# TDT_CableTester.net
KiCad netlist of a schematic drawn in EAGLE
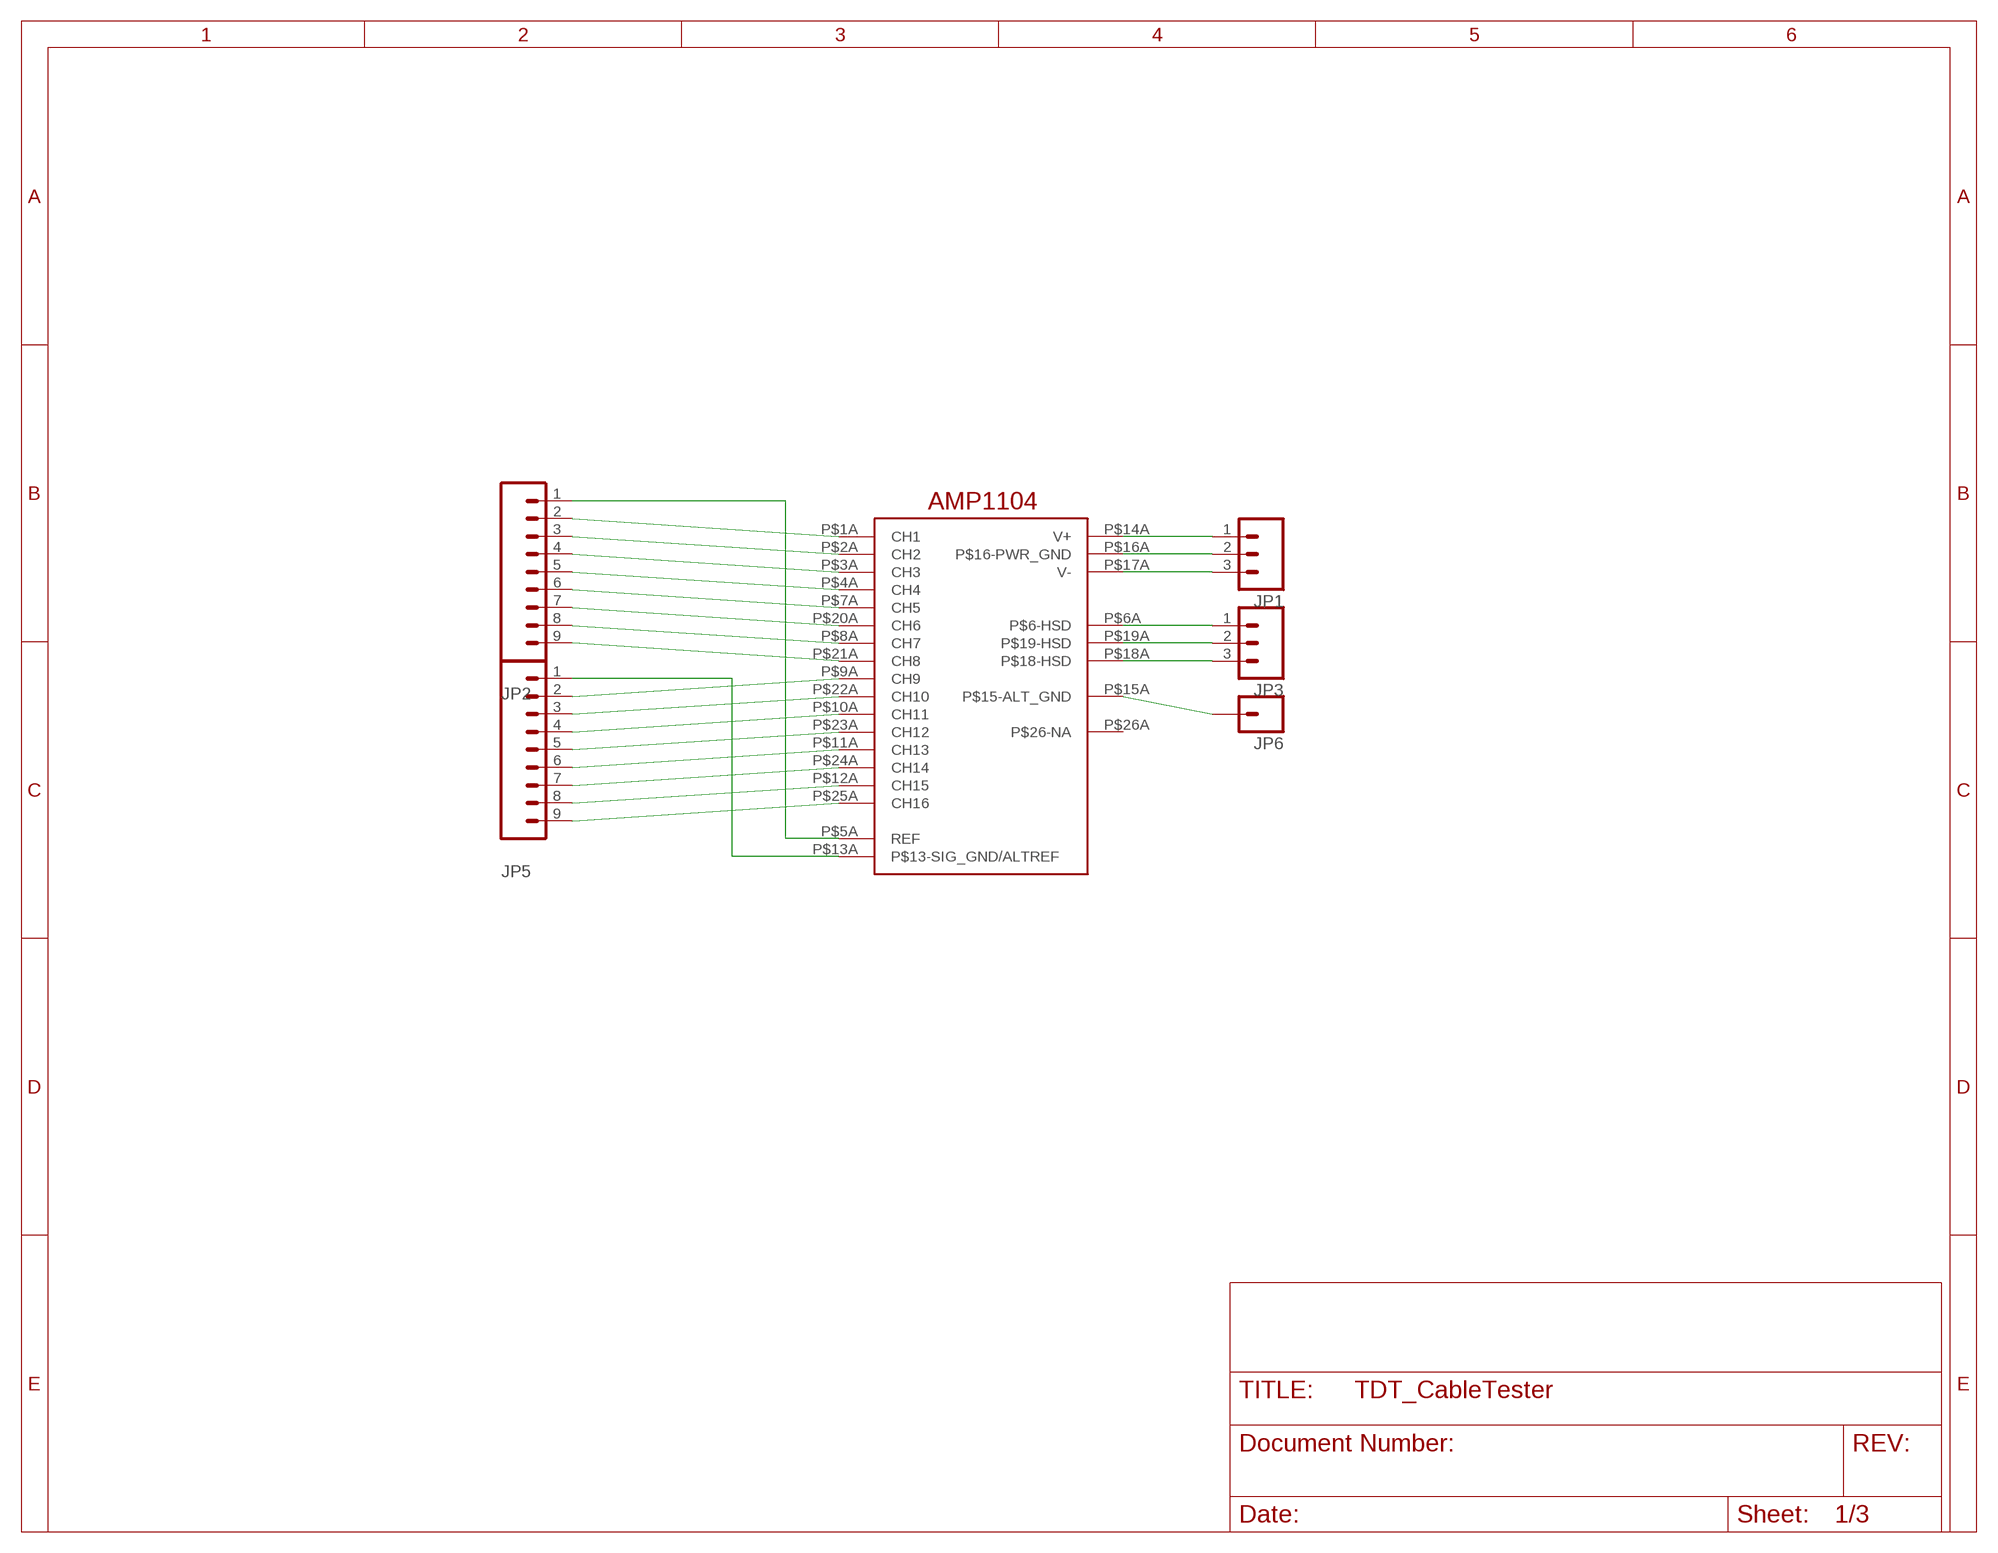
[diagram p0: schematic, sheet 1]

(export (version "E")
  (design (tool "Eeschema 10.0.6"))
  (components
    (comp (ref "JP1")
      (value "M03PTH")
      (footprint "eagle-import:1X03")
      (libsource (lib "eagle-import") (part "M03PTH"))
    )
    (comp (ref "JP2")
      (value "M09")
      (footprint "eagle-import:1X09")
      (libsource (lib "eagle-import") (part "M09"))
    )
    (comp (ref "JP3")
      (value "M03PTH")
      (footprint "eagle-import:1X03")
      (libsource (lib "eagle-import") (part "M03PTH"))
    )
    (comp (ref "JP5")
      (value "M09")
      (footprint "eagle-import:1X09")
      (libsource (lib "eagle-import") (part "M09"))
    )
    (comp (ref "JP6")
      (value "M01PTH")
      (footprint "eagle-import:1X01")
      (libsource (lib "eagle-import") (part "M01PTH"))
    )
    (comp (ref "U$3")
      (value "AMP1104")
      (footprint "eagle-import:AMP1104")
      (libsource (lib "eagle-import") (part "AMP1104"))
    )
  )
  (nets
    (net (code "1") (name "Net-(U$3-CH1)") (class "Default")
      (node (ref "JP2") (pin "2") (pinfunction "2_2") (pintype "passive"))
      (node (ref "U$3") (pin "P$1A") (pinfunction "CH1_P$1A") (pintype "bidirectional"))
    )
    (net (code "2") (name "Net-(U$3-CH2)") (class "Default")
      (node (ref "JP2") (pin "3") (pinfunction "3_3") (pintype "passive"))
      (node (ref "U$3") (pin "P$2A") (pinfunction "CH2_P$2A") (pintype "bidirectional"))
    )
    (net (code "3") (name "Net-(U$3-CH3)") (class "Default")
      (node (ref "JP2") (pin "4") (pinfunction "4_4") (pintype "passive"))
      (node (ref "U$3") (pin "P$3A") (pinfunction "CH3_P$3A") (pintype "bidirectional"))
    )
    (net (code "4") (name "Net-(U$3-CH4)") (class "Default")
      (node (ref "JP2") (pin "5") (pinfunction "5_5") (pintype "passive"))
      (node (ref "U$3") (pin "P$4A") (pinfunction "CH4_P$4A") (pintype "bidirectional"))
    )
    (net (code "5") (name "Net-(U$3-CH5)") (class "Default")
      (node (ref "JP2") (pin "6") (pinfunction "6_6") (pintype "passive"))
      (node (ref "U$3") (pin "P$7A") (pinfunction "CH5_P$7A") (pintype "bidirectional"))
    )
    (net (code "6") (name "Net-(U$3-CH6)") (class "Default")
      (node (ref "JP2") (pin "7") (pinfunction "7_7") (pintype "passive"))
      (node (ref "U$3") (pin "P$20A") (pinfunction "CH6_P$20A") (pintype "bidirectional"))
    )
    (net (code "7") (name "Net-(U$3-CH7)") (class "Default")
      (node (ref "JP2") (pin "8") (pinfunction "8_8") (pintype "passive"))
      (node (ref "U$3") (pin "P$8A") (pinfunction "CH7_P$8A") (pintype "bidirectional"))
    )
    (net (code "8") (name "Net-(U$3-CH8)") (class "Default")
      (node (ref "JP2") (pin "9") (pinfunction "9_9") (pintype "passive"))
      (node (ref "U$3") (pin "P$21A") (pinfunction "CH8_P$21A") (pintype "bidirectional"))
    )
    (net (code "9") (name "Net-(U$3-CH9)") (class "Default")
      (node (ref "JP5") (pin "2") (pinfunction "2_2") (pintype "passive"))
      (node (ref "U$3") (pin "P$9A") (pinfunction "CH9_P$9A") (pintype "bidirectional"))
    )
    (net (code "10") (name "Net-(U$3-CH10)") (class "Default")
      (node (ref "JP5") (pin "3") (pinfunction "3_3") (pintype "passive"))
      (node (ref "U$3") (pin "P$22A") (pinfunction "CH10_P$22A") (pintype "bidirectional"))
    )
    (net (code "11") (name "Net-(U$3-CH11)") (class "Default")
      (node (ref "JP5") (pin "4") (pinfunction "4_4") (pintype "passive"))
      (node (ref "U$3") (pin "P$10A") (pinfunction "CH11_P$10A") (pintype "bidirectional"))
    )
    (net (code "12") (name "Net-(U$3-CH12)") (class "Default")
      (node (ref "JP5") (pin "5") (pinfunction "5_5") (pintype "passive"))
      (node (ref "U$3") (pin "P$23A") (pinfunction "CH12_P$23A") (pintype "bidirectional"))
    )
    (net (code "13") (name "Net-(U$3-CH13)") (class "Default")
      (node (ref "JP5") (pin "6") (pinfunction "6_6") (pintype "passive"))
      (node (ref "U$3") (pin "P$11A") (pinfunction "CH13_P$11A") (pintype "bidirectional"))
    )
    (net (code "14") (name "Net-(U$3-CH14)") (class "Default")
      (node (ref "JP5") (pin "7") (pinfunction "7_7") (pintype "passive"))
      (node (ref "U$3") (pin "P$24A") (pinfunction "CH14_P$24A") (pintype "bidirectional"))
    )
    (net (code "15") (name "Net-(U$3-CH15)") (class "Default")
      (node (ref "JP5") (pin "8") (pinfunction "8_8") (pintype "passive"))
      (node (ref "U$3") (pin "P$12A") (pinfunction "CH15_P$12A") (pintype "bidirectional"))
    )
    (net (code "16") (name "Net-(U$3-CH16)") (class "Default")
      (node (ref "JP5") (pin "9") (pinfunction "9_9") (pintype "passive"))
      (node (ref "U$3") (pin "P$25A") (pinfunction "CH16_P$25A") (pintype "bidirectional"))
    )
    (net (code "17") (name "Net-(U$3-P$6-HSD)") (class "Default")
      (node (ref "JP3") (pin "1") (pinfunction "1_1") (pintype "passive"))
      (node (ref "U$3") (pin "P$6A") (pinfunction "P$6-HSD_P$6A") (pintype "bidirectional"))
    )
    (net (code "18") (name "Net-(U$3-P$13-SIG_GND{slash}ALTREF)") (class "Default")
      (node (ref "JP5") (pin "1") (pinfunction "1_1") (pintype "passive"))
      (node (ref "U$3") (pin "P$13A") (pinfunction "P$13-SIG_GND/ALTREF_P$13A") (pintype "bidirectional"))
    )
    (net (code "19") (name "Net-(U$3-P$15-ALT_GND)") (class "Default")
      (node (ref "JP6") (pin "1") (pinfunction "1_1") (pintype "passive"))
      (node (ref "U$3") (pin "P$15A") (pinfunction "P$15-ALT_GND_P$15A") (pintype "bidirectional"))
    )
    (net (code "20") (name "Net-(U$3-P$16-PWR_GND)") (class "Default")
      (node (ref "JP1") (pin "2") (pinfunction "2_2") (pintype "passive"))
      (node (ref "U$3") (pin "P$16A") (pinfunction "P$16-PWR_GND_P$16A") (pintype "bidirectional"))
    )
    (net (code "21") (name "Net-(U$3-P$18-HSD)") (class "Default")
      (node (ref "JP3") (pin "3") (pinfunction "3_3") (pintype "passive"))
      (node (ref "U$3") (pin "P$18A") (pinfunction "P$18-HSD_P$18A") (pintype "bidirectional"))
    )
    (net (code "22") (name "Net-(U$3-P$19-HSD)") (class "Default")
      (node (ref "JP3") (pin "2") (pinfunction "2_2") (pintype "passive"))
      (node (ref "U$3") (pin "P$19A") (pinfunction "P$19-HSD_P$19A") (pintype "bidirectional"))
    )
    (net (code "23") (name "Net-(U$3-REF)") (class "Default")
      (node (ref "JP2") (pin "1") (pinfunction "1_1") (pintype "passive"))
      (node (ref "U$3") (pin "P$5A") (pinfunction "REF_P$5A") (pintype "bidirectional"))
    )
    (net (code "24") (name "Net-(U$3-V+)") (class "Default")
      (node (ref "JP1") (pin "1") (pinfunction "1_1") (pintype "passive"))
      (node (ref "U$3") (pin "P$14A") (pinfunction "V+_P$14A") (pintype "bidirectional"))
    )
    (net (code "25") (name "Net-(U$3-V-)") (class "Default")
      (node (ref "JP1") (pin "3") (pinfunction "3_3") (pintype "passive"))
      (node (ref "U$3") (pin "P$17A") (pinfunction "V-_P$17A") (pintype "bidirectional"))
    )
    (net (code "26") (name "unconnected-(U$3-P$26-NA-PadP$26A)") (class "Default")
      (node (ref "U$3") (pin "P$26A") (pinfunction "P$26-NA_P$26A") (pintype "bidirectional"))
    )
  )
)
